# mcu-io.net
KiCad netlist of a schematic drawn in Altium Designer
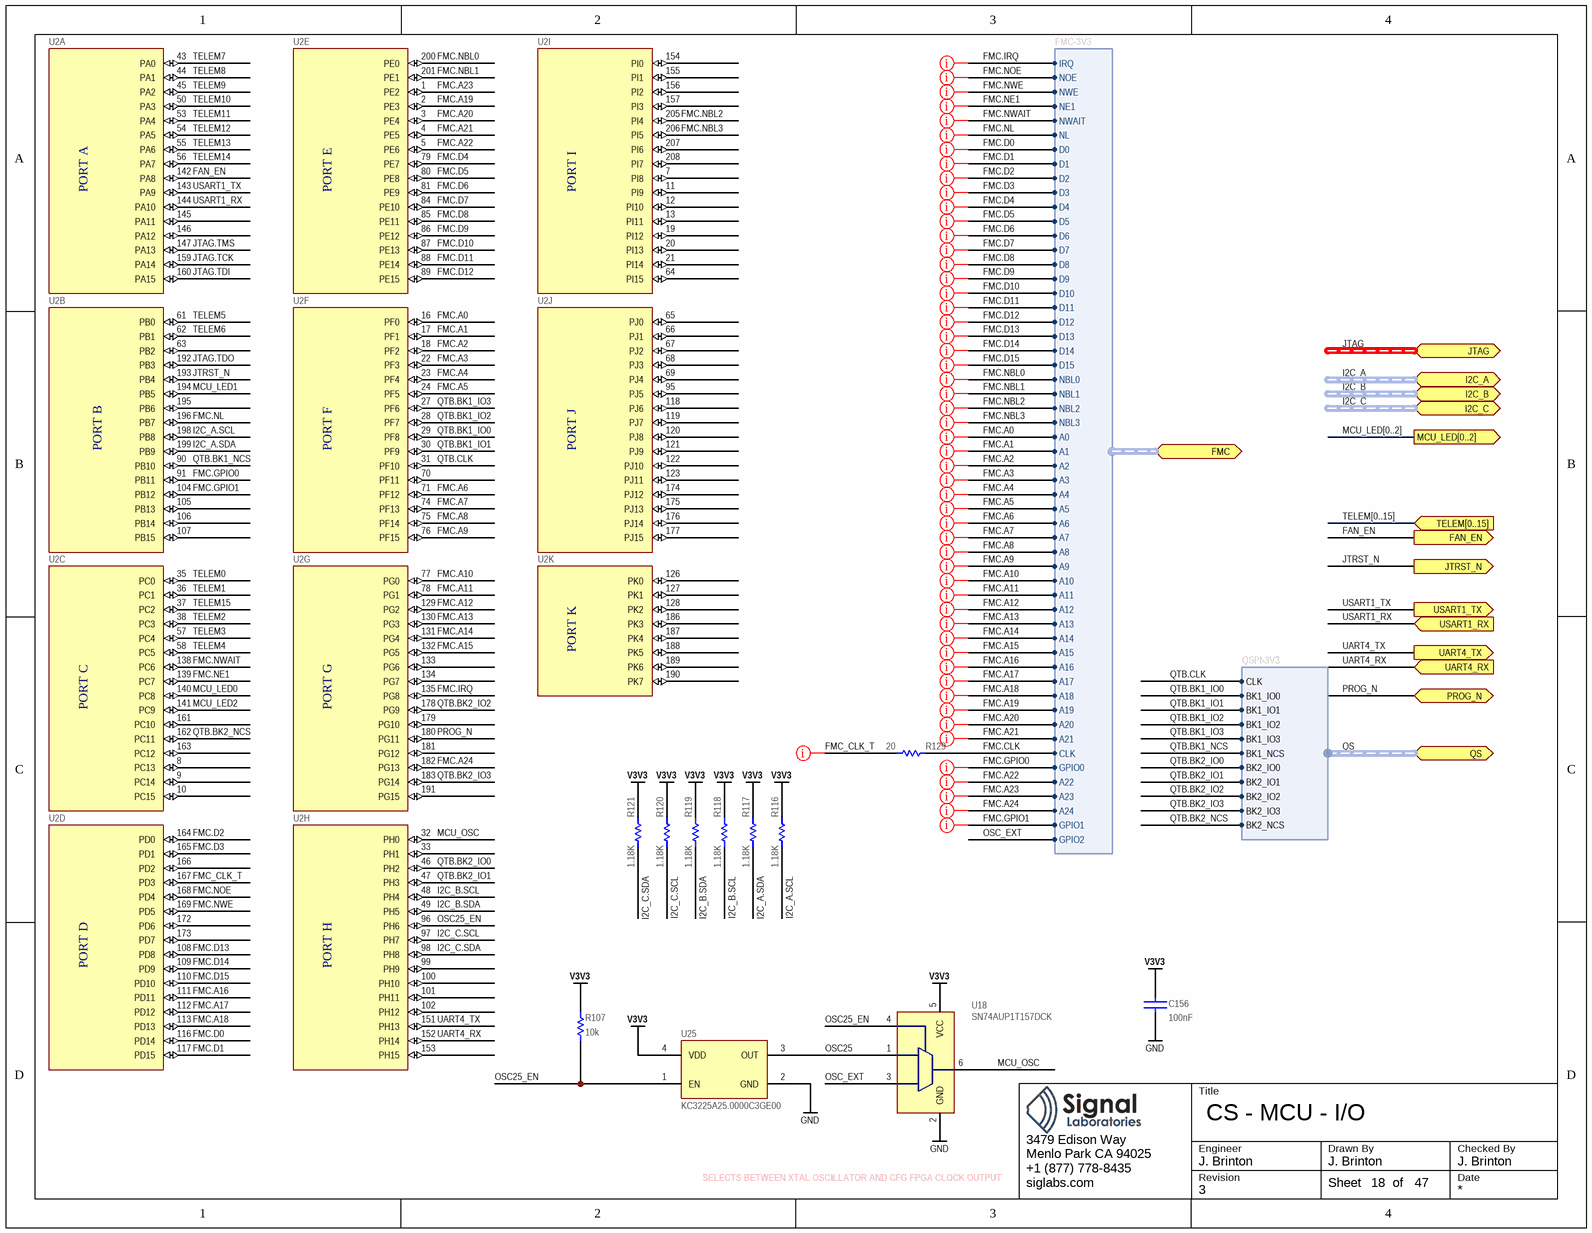
[diagram p0: mcu-io.SchDoc]

(export (version "E")
  (design (tool "Eeschema 10.0.6"))
  (components
    (comp (ref "C156")
      (value "100nF")
      (footprint "CAPC100X50X55L25N")
      (description "Ceramic Capacitor 100nF ±10% 50V X7R 0402")
      (fields (field (name "VOLTAGE") "50V") (field (name "MANUFACTURER") "Murata"))
      (libsource (lib "generic") (part "CAP"))
    )
    (comp (ref "R107")
      (value "10k")
      (footprint "RESC1005X40N")
      (description "Thick Film Resistor 10k ±1% 0.1W 50V 0402")
      (fields (field (name "MANUFACTURER") "Panasonic") (field (name "TOLERANCE") "±1%"))
      (libsource (lib "generic") (part "RES"))
    )
    (comp (ref "R116")
      (value "1.18K")
      (footprint "generic:RESC1005X40N")
      (description "Thick Film Resistor 1.18k ±1% 0402")
      (fields (field (name "MANUFACTURER") "Yageo") (field (name "TOLERANCE") "±1%"))
      (libsource (lib "Graviton") (part "RES 0402"))
    )
    (comp (ref "R117")
      (value "1.18K")
      (footprint "generic:RESC1005X40N")
      (description "Thick Film Resistor 1.18k ±1% 0402")
      (fields (field (name "MANUFACTURER") "Yageo") (field (name "TOLERANCE") "±1%"))
      (libsource (lib "Graviton") (part "RES 0402"))
    )
    (comp (ref "R118")
      (value "1.18K")
      (footprint "generic:RESC1005X40N")
      (description "Thick Film Resistor 1.18k ±1% 0402")
      (fields (field (name "MANUFACTURER") "Yageo") (field (name "TOLERANCE") "±1%"))
      (libsource (lib "Graviton") (part "RES 0402"))
    )
    (comp (ref "R119")
      (value "1.18K")
      (footprint "generic:RESC1005X40N")
      (description "Thick Film Resistor 1.18k ±1% 0402")
      (fields (field (name "MANUFACTURER") "Yageo") (field (name "TOLERANCE") "±1%"))
      (libsource (lib "Graviton") (part "RES 0402"))
    )
    (comp (ref "R120")
      (value "1.18K")
      (footprint "generic:RESC1005X40N")
      (description "Thick Film Resistor 1.18k ±1% 0402")
      (fields (field (name "MANUFACTURER") "Yageo") (field (name "TOLERANCE") "±1%"))
      (libsource (lib "Graviton") (part "RES 0402"))
    )
    (comp (ref "R121")
      (value "1.18K")
      (footprint "generic:RESC1005X40N")
      (description "Thick Film Resistor 1.18k ±1% 0402")
      (fields (field (name "MANUFACTURER") "Yageo") (field (name "TOLERANCE") "±1%"))
      (libsource (lib "Graviton") (part "RES 0402"))
    )
    (comp (ref "R129")
      (value "20")
      (footprint "RESC1005X40N")
      (description "Thick Film Resistor 20 ±1% 0.1W 75V 0402")
      (fields (field (name "TOLERANCE") "±1%") (field (name "MANUFACTURER") "Panasonic"))
      (libsource (lib "generic") (part "RES"))
    )
    (comp (ref "U2")
      (value "STM32F779BI")
      (footprint "LQFP208")
      (description "STM32 Microcontroller")
      (fields (field (name "MANUFACTURER") "ST Microelectronics"))
      (libsource (lib "hadley") (part "STM32F746BGT6"))
    )
    (comp (ref "U18")
      (value "SN74AUP1T157DCK")
      (footprint "generic:SOT363")
      (description "Buffer Multiplexer")
      (fields (field (name "MANUFACTURER") "Texas Instruments"))
      (libsource (lib "ti") (part "SN74AUP1T157DCK"))
    )
    (comp (ref "U25")
      (value "KC3225A25.0000C3GE00")
      (footprint "OSCCC320X250X80L75X100N")
      (description "Oscillator 25.00Mhz, -+50PPM, 3.3V")
      (fields (field (name "MANUFACTURER") "Kyocera"))
      (libsource (lib "MCD_TOOLS") (part "OSC_25M_NZ2520SB"))
    )
  )
  (nets
    (net (code "7") (name "/FAN_EN") (class "Default")
      (node (ref "U2") (pin "142") (pinfunction "PA8_142") (pintype "bidirectional"))
    )
    (net (code "8") (name "/FMC.A0") (class "Default")
      (node (ref "U2") (pin "16") (pinfunction "PF0_16") (pintype "bidirectional"))
    )
    (net (code "9") (name "/FMC.A1") (class "Default")
      (node (ref "U2") (pin "17") (pinfunction "PF1_17") (pintype "bidirectional"))
    )
    (net (code "10") (name "/FMC.A2") (class "Default")
      (node (ref "U2") (pin "18") (pinfunction "PF2_18") (pintype "bidirectional"))
    )
    (net (code "11") (name "/FMC.A3") (class "Default")
      (node (ref "U2") (pin "22") (pinfunction "PF3_22") (pintype "bidirectional"))
    )
    (net (code "12") (name "/FMC.A4") (class "Default")
      (node (ref "U2") (pin "23") (pinfunction "PF4_23") (pintype "bidirectional"))
    )
    (net (code "13") (name "/FMC.A5") (class "Default")
      (node (ref "U2") (pin "24") (pinfunction "PF5_24") (pintype "bidirectional"))
    )
    (net (code "14") (name "/FMC.A6") (class "Default")
      (node (ref "U2") (pin "71") (pinfunction "PF12_71") (pintype "bidirectional"))
    )
    (net (code "15") (name "/FMC.A7") (class "Default")
      (node (ref "U2") (pin "74") (pinfunction "PF13_74") (pintype "bidirectional"))
    )
    (net (code "16") (name "/FMC.A8") (class "Default")
      (node (ref "U2") (pin "75") (pinfunction "PF14_75") (pintype "bidirectional"))
    )
    (net (code "17") (name "/FMC.A9") (class "Default")
      (node (ref "U2") (pin "76") (pinfunction "PF15_76") (pintype "bidirectional"))
    )
    (net (code "18") (name "/FMC.A10") (class "Default")
      (node (ref "U2") (pin "77") (pinfunction "PG0_77") (pintype "bidirectional"))
    )
    (net (code "19") (name "/FMC.A11") (class "Default")
      (node (ref "U2") (pin "78") (pinfunction "PG1_78") (pintype "bidirectional"))
    )
    (net (code "20") (name "/FMC.A12") (class "Default")
      (node (ref "U2") (pin "129") (pinfunction "PG2_129") (pintype "bidirectional"))
    )
    (net (code "21") (name "/FMC.A13") (class "Default")
      (node (ref "U2") (pin "130") (pinfunction "PG3_130") (pintype "bidirectional"))
    )
    (net (code "22") (name "/FMC.A14") (class "Default")
      (node (ref "U2") (pin "131") (pinfunction "PG4_131") (pintype "bidirectional"))
    )
    (net (code "23") (name "/FMC.A15") (class "Default")
      (node (ref "U2") (pin "132") (pinfunction "PG5_132") (pintype "bidirectional"))
    )
    (net (code "24") (name "/FMC.A16") (class "Default")
      (node (ref "U2") (pin "111") (pinfunction "PD11_111") (pintype "bidirectional"))
    )
    (net (code "25") (name "/FMC.A17") (class "Default")
      (node (ref "U2") (pin "112") (pinfunction "PD12_112") (pintype "bidirectional"))
    )
    (net (code "26") (name "/FMC.A18") (class "Default")
      (node (ref "U2") (pin "113") (pinfunction "PD13_113") (pintype "bidirectional"))
    )
    (net (code "27") (name "/FMC.A19") (class "Default")
      (node (ref "U2") (pin "2") (pinfunction "PE3_2") (pintype "bidirectional"))
    )
    (net (code "28") (name "/FMC.A20") (class "Default")
      (node (ref "U2") (pin "3") (pinfunction "PE4_3") (pintype "bidirectional"))
    )
    (net (code "29") (name "/FMC.A21") (class "Default")
      (node (ref "U2") (pin "4") (pinfunction "PE5_4") (pintype "bidirectional"))
    )
    (net (code "30") (name "/FMC.A22") (class "Default")
      (node (ref "U2") (pin "5") (pinfunction "PE6_5") (pintype "bidirectional"))
    )
    (net (code "31") (name "/FMC.A23") (class "Default")
      (node (ref "U2") (pin "1") (pinfunction "PE2_1") (pintype "bidirectional"))
    )
    (net (code "32") (name "/FMC.A24") (class "Default")
      (node (ref "U2") (pin "182") (pinfunction "PG13_182") (pintype "bidirectional"))
    )
    (net (code "33") (name "/FMC.CLK") (class "Default")
      (node (ref "R129") (pin "2") (pinfunction "2_2") (pintype "passive"))
    )
    (net (code "34") (name "/FMC.D0") (class "Default")
      (node (ref "U2") (pin "116") (pinfunction "PD14_116") (pintype "bidirectional"))
    )
    (net (code "35") (name "/FMC.D1") (class "Default")
      (node (ref "U2") (pin "117") (pinfunction "PD15_117") (pintype "bidirectional"))
    )
    (net (code "36") (name "/FMC.D2") (class "Default")
      (node (ref "U2") (pin "164") (pinfunction "PD0_164") (pintype "bidirectional"))
    )
    (net (code "37") (name "/FMC.D3") (class "Default")
      (node (ref "U2") (pin "165") (pinfunction "PD1_165") (pintype "bidirectional"))
    )
    (net (code "38") (name "/FMC.D4") (class "Default")
      (node (ref "U2") (pin "79") (pinfunction "PE7_79") (pintype "bidirectional"))
    )
    (net (code "39") (name "/FMC.D5") (class "Default")
      (node (ref "U2") (pin "80") (pinfunction "PE8_80") (pintype "bidirectional"))
    )
    (net (code "40") (name "/FMC.D6") (class "Default")
      (node (ref "U2") (pin "81") (pinfunction "PE9_81") (pintype "bidirectional"))
    )
    (net (code "41") (name "/FMC.D7") (class "Default")
      (node (ref "U2") (pin "84") (pinfunction "PE10_84") (pintype "bidirectional"))
    )
    (net (code "42") (name "/FMC.D8") (class "Default")
      (node (ref "U2") (pin "85") (pinfunction "PE11_85") (pintype "bidirectional"))
    )
    (net (code "43") (name "/FMC.D9") (class "Default")
      (node (ref "U2") (pin "86") (pinfunction "PE12_86") (pintype "bidirectional"))
    )
    (net (code "44") (name "/FMC.D10") (class "Default")
      (node (ref "U2") (pin "87") (pinfunction "PE13_87") (pintype "bidirectional"))
    )
    (net (code "45") (name "/FMC.D11") (class "Default")
      (node (ref "U2") (pin "88") (pinfunction "PE14_88") (pintype "bidirectional"))
    )
    (net (code "46") (name "/FMC.D12") (class "Default")
      (node (ref "U2") (pin "89") (pinfunction "PE15_89") (pintype "bidirectional"))
    )
    (net (code "47") (name "/FMC.D13") (class "Default")
      (node (ref "U2") (pin "108") (pinfunction "PD8_108") (pintype "bidirectional"))
    )
    (net (code "48") (name "/FMC.D14") (class "Default")
      (node (ref "U2") (pin "109") (pinfunction "PD9_109") (pintype "bidirectional"))
    )
    (net (code "49") (name "/FMC.D15") (class "Default")
      (node (ref "U2") (pin "110") (pinfunction "PD10_110") (pintype "bidirectional"))
    )
    (net (code "50") (name "/FMC.GPIO0") (class "Default")
      (node (ref "U2") (pin "91") (pinfunction "PB11_91") (pintype "bidirectional"))
    )
    (net (code "51") (name "/FMC.GPIO1") (class "Default")
      (node (ref "U2") (pin "104") (pinfunction "PB12_104") (pintype "bidirectional"))
    )
    (net (code "52") (name "/FMC.IRQ") (class "Default")
      (node (ref "U2") (pin "135") (pinfunction "PG8_135") (pintype "bidirectional"))
    )
    (net (code "53") (name "/FMC.NBL0") (class "Default")
      (node (ref "U2") (pin "200") (pinfunction "PE0_200") (pintype "bidirectional"))
    )
    (net (code "54") (name "/FMC.NBL1") (class "Default")
      (node (ref "U2") (pin "201") (pinfunction "PE1_201") (pintype "bidirectional"))
    )
    (net (code "55") (name "/FMC.NBL2") (class "Default")
      (node (ref "U2") (pin "205") (pinfunction "PI4_205") (pintype "bidirectional"))
    )
    (net (code "56") (name "/FMC.NBL3") (class "Default")
      (node (ref "U2") (pin "206") (pinfunction "PI5_206") (pintype "bidirectional"))
    )
    (net (code "57") (name "/FMC.NE1") (class "Default")
      (node (ref "U2") (pin "139") (pinfunction "PC7_139") (pintype "bidirectional"))
    )
    (net (code "58") (name "/FMC.NL") (class "Default")
      (node (ref "U2") (pin "196") (pinfunction "PB7_196") (pintype "bidirectional"))
    )
    (net (code "59") (name "/FMC.NOE") (class "Default")
      (node (ref "U2") (pin "168") (pinfunction "PD4_168") (pintype "bidirectional"))
    )
    (net (code "60") (name "/FMC.NWAIT") (class "Default")
      (node (ref "U2") (pin "138") (pinfunction "PC6_138") (pintype "bidirectional"))
    )
    (net (code "61") (name "/FMC.NWE") (class "Default")
      (node (ref "U2") (pin "169") (pinfunction "PD5_169") (pintype "bidirectional"))
    )
    (net (code "62") (name "/FMC_CLK_T") (class "Default")
      (node (ref "R129") (pin "1") (pinfunction "1_1") (pintype "passive"))
      (node (ref "U2") (pin "167") (pinfunction "PD3_167") (pintype "bidirectional"))
    )
    (net (code "63") (name "/I2C_A.SCL") (class "Default")
      (node (ref "R116") (pin "1") (pinfunction "1_1") (pintype "passive"))
      (node (ref "U2") (pin "198") (pinfunction "PB8_198") (pintype "bidirectional"))
    )
    (net (code "64") (name "/I2C_A.SDA") (class "Default")
      (node (ref "R117") (pin "1") (pinfunction "1_1") (pintype "passive"))
      (node (ref "U2") (pin "199") (pinfunction "PB9_199") (pintype "bidirectional"))
    )
    (net (code "65") (name "/I2C_B.SCL") (class "Default")
      (node (ref "R118") (pin "1") (pinfunction "1_1") (pintype "passive"))
      (node (ref "U2") (pin "48") (pinfunction "PH4_48") (pintype "bidirectional"))
    )
    (net (code "66") (name "/I2C_B.SDA") (class "Default")
      (node (ref "R119") (pin "1") (pinfunction "1_1") (pintype "passive"))
      (node (ref "U2") (pin "49") (pinfunction "PH5_49") (pintype "bidirectional"))
    )
    (net (code "67") (name "/I2C_C.SCL") (class "Default")
      (node (ref "R120") (pin "1") (pinfunction "1_1") (pintype "passive"))
      (node (ref "U2") (pin "97") (pinfunction "PH7_97") (pintype "bidirectional"))
    )
    (net (code "68") (name "/I2C_C.SDA") (class "Default")
      (node (ref "R121") (pin "1") (pinfunction "1_1") (pintype "passive"))
      (node (ref "U2") (pin "98") (pinfunction "PH8_98") (pintype "bidirectional"))
    )
    (net (code "69") (name "/JTAG.TCK") (class "Default")
      (node (ref "U2") (pin "159") (pinfunction "PA14_159") (pintype "bidirectional"))
    )
    (net (code "70") (name "/JTAG.TDI") (class "Default")
      (node (ref "U2") (pin "160") (pinfunction "PA15_160") (pintype "bidirectional"))
    )
    (net (code "71") (name "/JTAG.TDO") (class "Default")
      (node (ref "U2") (pin "192") (pinfunction "PB3_192") (pintype "bidirectional"))
    )
    (net (code "72") (name "/JTAG.TMS") (class "Default")
      (node (ref "U2") (pin "147") (pinfunction "PA13_147") (pintype "bidirectional"))
    )
    (net (code "73") (name "/JTRST_N") (class "Default")
      (node (ref "U2") (pin "193") (pinfunction "PB4_193") (pintype "bidirectional"))
    )
    (net (code "74") (name "/MCU_LED0") (class "Default")
      (node (ref "U2") (pin "140") (pinfunction "PC8_140") (pintype "bidirectional"))
    )
    (net (code "75") (name "/MCU_LED1") (class "Default")
      (node (ref "U2") (pin "194") (pinfunction "PB5_194") (pintype "bidirectional"))
    )
    (net (code "76") (name "/MCU_LED2") (class "Default")
      (node (ref "U2") (pin "141") (pinfunction "PC9_141") (pintype "bidirectional"))
    )
    (net (code "78") (name "/MCU_OSC") (class "Default")
      (node (ref "U18") (pin "6") (pinfunction "Y_6") (pintype "passive"))
      (node (ref "U2") (pin "32") (pinfunction "PH0_32") (pintype "bidirectional"))
    )
    (net (code "79") (name "/OSC25") (class "Default")
      (node (ref "U18") (pin "1") (pinfunction "A_1") (pintype "passive"))
      (node (ref "U25") (pin "3") (pinfunction "OUT_3") (pintype "passive"))
    )
    (net (code "80") (name "/OSC25_EN") (class "Default")
      (node (ref "R107") (pin "1") (pinfunction "1_1") (pintype "passive"))
      (node (ref "U18") (pin "4") (pinfunction "C_4") (pintype "passive"))
      (node (ref "U2") (pin "96") (pinfunction "PH6_96") (pintype "bidirectional"))
      (node (ref "U25") (pin "1") (pinfunction "EN_1") (pintype "passive"))
    )
    (net (code "81") (name "/OSC_EXT") (class "Default")
      (node (ref "U18") (pin "3") (pinfunction "B_3") (pintype "passive"))
    )
    (net (code "82") (name "/PROG_N") (class "Default")
      (node (ref "U2") (pin "180") (pinfunction "PG11_180") (pintype "bidirectional"))
    )
    (net (code "84") (name "/QTB.BK1_IO0") (class "Default")
      (node (ref "U2") (pin "29") (pinfunction "PF8_29") (pintype "bidirectional"))
    )
    (net (code "85") (name "/QTB.BK1_IO1") (class "Default")
      (node (ref "U2") (pin "30") (pinfunction "PF9_30") (pintype "bidirectional"))
    )
    (net (code "86") (name "/QTB.BK1_IO2") (class "Default")
      (node (ref "U2") (pin "28") (pinfunction "PF7_28") (pintype "bidirectional"))
    )
    (net (code "87") (name "/QTB.BK1_IO3") (class "Default")
      (node (ref "U2") (pin "27") (pinfunction "PF6_27") (pintype "bidirectional"))
    )
    (net (code "88") (name "/QTB.BK1_NCS") (class "Default")
      (node (ref "U2") (pin "90") (pinfunction "PB10_90") (pintype "bidirectional"))
    )
    (net (code "89") (name "/QTB.BK2_IO0") (class "Default")
      (node (ref "U2") (pin "46") (pinfunction "PH2_46") (pintype "bidirectional"))
    )
    (net (code "90") (name "/QTB.BK2_IO1") (class "Default")
      (node (ref "U2") (pin "47") (pinfunction "PH3_47") (pintype "bidirectional"))
    )
    (net (code "91") (name "/QTB.BK2_IO2") (class "Default")
      (node (ref "U2") (pin "178") (pinfunction "PG9_178") (pintype "bidirectional"))
    )
    (net (code "92") (name "/QTB.BK2_IO3") (class "Default")
      (node (ref "U2") (pin "183") (pinfunction "PG14_183") (pintype "bidirectional"))
    )
    (net (code "93") (name "/QTB.BK2_NCS") (class "Default")
      (node (ref "U2") (pin "162") (pinfunction "PC11_162") (pintype "bidirectional"))
    )
    (net (code "94") (name "/QTB.CLK") (class "Default")
      (node (ref "U2") (pin "31") (pinfunction "PF10_31") (pintype "bidirectional"))
    )
    (net (code "95") (name "/TELEM0") (class "Default")
      (node (ref "U2") (pin "35") (pinfunction "PC0_35") (pintype "bidirectional"))
    )
    (net (code "96") (name "/TELEM1") (class "Default")
      (node (ref "U2") (pin "36") (pinfunction "PC1_36") (pintype "bidirectional"))
    )
    (net (code "97") (name "/TELEM2") (class "Default")
      (node (ref "U2") (pin "38") (pinfunction "PC3_38") (pintype "bidirectional"))
    )
    (net (code "98") (name "/TELEM3") (class "Default")
      (node (ref "U2") (pin "57") (pinfunction "PC4_57") (pintype "bidirectional"))
    )
    (net (code "99") (name "/TELEM4") (class "Default")
      (node (ref "U2") (pin "58") (pinfunction "PC5_58") (pintype "bidirectional"))
    )
    (net (code "100") (name "/TELEM5") (class "Default")
      (node (ref "U2") (pin "61") (pinfunction "PB0_61") (pintype "bidirectional"))
    )
    (net (code "101") (name "/TELEM6") (class "Default")
      (node (ref "U2") (pin "62") (pinfunction "PB1_62") (pintype "bidirectional"))
    )
    (net (code "102") (name "/TELEM7") (class "Default")
      (node (ref "U2") (pin "43") (pinfunction "PA0_43") (pintype "bidirectional"))
    )
    (net (code "103") (name "/TELEM8") (class "Default")
      (node (ref "U2") (pin "44") (pinfunction "PA1_44") (pintype "bidirectional"))
    )
    (net (code "104") (name "/TELEM9") (class "Default")
      (node (ref "U2") (pin "45") (pinfunction "PA2_45") (pintype "bidirectional"))
    )
    (net (code "105") (name "/TELEM10") (class "Default")
      (node (ref "U2") (pin "50") (pinfunction "PA3_50") (pintype "bidirectional"))
    )
    (net (code "106") (name "/TELEM11") (class "Default")
      (node (ref "U2") (pin "53") (pinfunction "PA4_53") (pintype "bidirectional"))
    )
    (net (code "107") (name "/TELEM12") (class "Default")
      (node (ref "U2") (pin "54") (pinfunction "PA5_54") (pintype "bidirectional"))
    )
    (net (code "108") (name "/TELEM13") (class "Default")
      (node (ref "U2") (pin "55") (pinfunction "PA6_55") (pintype "bidirectional"))
    )
    (net (code "109") (name "/TELEM14") (class "Default")
      (node (ref "U2") (pin "56") (pinfunction "PA7_56") (pintype "bidirectional"))
    )
    (net (code "110") (name "/TELEM15") (class "Default")
      (node (ref "U2") (pin "37") (pinfunction "PC2_37") (pintype "bidirectional"))
    )
    (net (code "112") (name "/UART4_RX") (class "Default")
      (node (ref "U2") (pin "152") (pinfunction "PH14_152") (pintype "bidirectional"))
    )
    (net (code "113") (name "/UART4_TX") (class "Default")
      (node (ref "U2") (pin "151") (pinfunction "PH13_151") (pintype "bidirectional"))
    )
    (net (code "114") (name "/USART1_RX") (class "Default")
      (node (ref "U2") (pin "144") (pinfunction "PA10_144") (pintype "bidirectional"))
    )
    (net (code "115") (name "/USART1_TX") (class "Default")
      (node (ref "U2") (pin "143") (pinfunction "PA9_143") (pintype "bidirectional"))
    )
    (net (code "121") (name "GND") (class "Default")
      (node (ref "C156") (pin "1") (pinfunction "1_1") (pintype "passive"))
      (node (ref "U18") (pin "2") (pinfunction "GND_2") (pintype "passive"))
      (node (ref "U25") (pin "2") (pinfunction "GND_2") (pintype "passive"))
    )
    (net (code "122") (name "V3V3") (class "Default")
      (node (ref "C156") (pin "2") (pinfunction "2_2") (pintype "passive"))
      (node (ref "R107") (pin "2") (pinfunction "2_2") (pintype "passive"))
      (node (ref "R116") (pin "2") (pinfunction "2_2") (pintype "passive"))
      (node (ref "R117") (pin "2") (pinfunction "2_2") (pintype "passive"))
      (node (ref "R118") (pin "2") (pinfunction "2_2") (pintype "passive"))
      (node (ref "R119") (pin "2") (pinfunction "2_2") (pintype "passive"))
      (node (ref "R120") (pin "2") (pinfunction "2_2") (pintype "passive"))
      (node (ref "R121") (pin "2") (pinfunction "2_2") (pintype "passive"))
      (node (ref "U18") (pin "5") (pinfunction "VCC_5") (pintype "passive"))
      (node (ref "U25") (pin "4") (pinfunction "VDD_4") (pintype "passive"))
    )
    (net (code "123") (name "unconnected-(U2A-PA11-Pad145)") (class "Default")
      (node (ref "U2") (pin "145") (pinfunction "PA11_145") (pintype "bidirectional"))
    )
    (net (code "124") (name "unconnected-(U2A-PA12-Pad146)") (class "Default")
      (node (ref "U2") (pin "146") (pinfunction "PA12_146") (pintype "bidirectional"))
    )
    (net (code "125") (name "unconnected-(U2B-PB2-Pad63)") (class "Default")
      (node (ref "U2") (pin "63") (pinfunction "PB2_63") (pintype "bidirectional"))
    )
    (net (code "126") (name "unconnected-(U2B-PB6-Pad195)") (class "Default")
      (node (ref "U2") (pin "195") (pinfunction "PB6_195") (pintype "bidirectional"))
    )
    (net (code "127") (name "unconnected-(U2B-PB13-Pad105)") (class "Default")
      (node (ref "U2") (pin "105") (pinfunction "PB13_105") (pintype "bidirectional"))
    )
    (net (code "128") (name "unconnected-(U2B-PB14-Pad106)") (class "Default")
      (node (ref "U2") (pin "106") (pinfunction "PB14_106") (pintype "bidirectional"))
    )
    (net (code "129") (name "unconnected-(U2B-PB15-Pad107)") (class "Default")
      (node (ref "U2") (pin "107") (pinfunction "PB15_107") (pintype "bidirectional"))
    )
    (net (code "130") (name "unconnected-(U2C-PC10-Pad161)") (class "Default")
      (node (ref "U2") (pin "161") (pinfunction "PC10_161") (pintype "bidirectional"))
    )
    (net (code "131") (name "unconnected-(U2C-PC12-Pad163)") (class "Default")
      (node (ref "U2") (pin "163") (pinfunction "PC12_163") (pintype "bidirectional"))
    )
    (net (code "132") (name "unconnected-(U2C-PC13-Pad8)") (class "Default")
      (node (ref "U2") (pin "8") (pinfunction "PC13_8") (pintype "bidirectional"))
    )
    (net (code "133") (name "unconnected-(U2C-PC14-Pad9)") (class "Default")
      (node (ref "U2") (pin "9") (pinfunction "PC14_9") (pintype "bidirectional"))
    )
    (net (code "134") (name "unconnected-(U2C-PC15-Pad10)") (class "Default")
      (node (ref "U2") (pin "10") (pinfunction "PC15_10") (pintype "bidirectional"))
    )
    (net (code "135") (name "unconnected-(U2D-PD2-Pad166)") (class "Default")
      (node (ref "U2") (pin "166") (pinfunction "PD2_166") (pintype "bidirectional"))
    )
    (net (code "136") (name "unconnected-(U2D-PD6-Pad172)") (class "Default")
      (node (ref "U2") (pin "172") (pinfunction "PD6_172") (pintype "bidirectional"))
    )
    (net (code "137") (name "unconnected-(U2D-PD7-Pad173)") (class "Default")
      (node (ref "U2") (pin "173") (pinfunction "PD7_173") (pintype "bidirectional"))
    )
    (net (code "138") (name "unconnected-(U2F-PF11-Pad70)") (class "Default")
      (node (ref "U2") (pin "70") (pinfunction "PF11_70") (pintype "bidirectional"))
    )
    (net (code "139") (name "unconnected-(U2G-PG6-Pad133)") (class "Default")
      (node (ref "U2") (pin "133") (pinfunction "PG6_133") (pintype "bidirectional"))
    )
    (net (code "140") (name "unconnected-(U2G-PG7-Pad134)") (class "Default")
      (node (ref "U2") (pin "134") (pinfunction "PG7_134") (pintype "bidirectional"))
    )
    (net (code "141") (name "unconnected-(U2G-PG10-Pad179)") (class "Default")
      (node (ref "U2") (pin "179") (pinfunction "PG10_179") (pintype "bidirectional"))
    )
    (net (code "142") (name "unconnected-(U2G-PG12-Pad181)") (class "Default")
      (node (ref "U2") (pin "181") (pinfunction "PG12_181") (pintype "bidirectional"))
    )
    (net (code "143") (name "unconnected-(U2G-PG15-Pad191)") (class "Default")
      (node (ref "U2") (pin "191") (pinfunction "PG15_191") (pintype "bidirectional"))
    )
    (net (code "144") (name "unconnected-(U2H-PH1-Pad33)") (class "Default")
      (node (ref "U2") (pin "33") (pinfunction "PH1_33") (pintype "bidirectional"))
    )
    (net (code "145") (name "unconnected-(U2H-PH9-Pad99)") (class "Default")
      (node (ref "U2") (pin "99") (pinfunction "PH9_99") (pintype "bidirectional"))
    )
    (net (code "146") (name "unconnected-(U2H-PH10-Pad100)") (class "Default")
      (node (ref "U2") (pin "100") (pinfunction "PH10_100") (pintype "bidirectional"))
    )
    (net (code "147") (name "unconnected-(U2H-PH11-Pad101)") (class "Default")
      (node (ref "U2") (pin "101") (pinfunction "PH11_101") (pintype "bidirectional"))
    )
    (net (code "148") (name "unconnected-(U2H-PH12-Pad102)") (class "Default")
      (node (ref "U2") (pin "102") (pinfunction "PH12_102") (pintype "bidirectional"))
    )
    (net (code "149") (name "unconnected-(U2H-PH15-Pad153)") (class "Default")
      (node (ref "U2") (pin "153") (pinfunction "PH15_153") (pintype "bidirectional"))
    )
    (net (code "150") (name "unconnected-(U2I-PI0-Pad154)") (class "Default")
      (node (ref "U2") (pin "154") (pinfunction "PI0_154") (pintype "bidirectional"))
    )
    (net (code "151") (name "unconnected-(U2I-PI1-Pad155)") (class "Default")
      (node (ref "U2") (pin "155") (pinfunction "PI1_155") (pintype "bidirectional"))
    )
    (net (code "152") (name "unconnected-(U2I-PI2-Pad156)") (class "Default")
      (node (ref "U2") (pin "156") (pinfunction "PI2_156") (pintype "bidirectional"))
    )
    (net (code "153") (name "unconnected-(U2I-PI3-Pad157)") (class "Default")
      (node (ref "U2") (pin "157") (pinfunction "PI3_157") (pintype "bidirectional"))
    )
    (net (code "154") (name "unconnected-(U2I-PI6-Pad207)") (class "Default")
      (node (ref "U2") (pin "207") (pinfunction "PI6_207") (pintype "bidirectional"))
    )
    (net (code "155") (name "unconnected-(U2I-PI7-Pad208)") (class "Default")
      (node (ref "U2") (pin "208") (pinfunction "PI7_208") (pintype "bidirectional"))
    )
    (net (code "156") (name "unconnected-(U2I-PI8-Pad7)") (class "Default")
      (node (ref "U2") (pin "7") (pinfunction "PI8_7") (pintype "bidirectional"))
    )
    (net (code "157") (name "unconnected-(U2I-PI9-Pad11)") (class "Default")
      (node (ref "U2") (pin "11") (pinfunction "PI9_11") (pintype "bidirectional"))
    )
    (net (code "158") (name "unconnected-(U2I-PI10-Pad12)") (class "Default")
      (node (ref "U2") (pin "12") (pinfunction "PI10_12") (pintype "bidirectional"))
    )
    (net (code "159") (name "unconnected-(U2I-PI11-Pad13)") (class "Default")
      (node (ref "U2") (pin "13") (pinfunction "PI11_13") (pintype "bidirectional"))
    )
    (net (code "160") (name "unconnected-(U2I-PI12-Pad19)") (class "Default")
      (node (ref "U2") (pin "19") (pinfunction "PI12_19") (pintype "bidirectional"))
    )
    (net (code "161") (name "unconnected-(U2I-PI13-Pad20)") (class "Default")
      (node (ref "U2") (pin "20") (pinfunction "PI13_20") (pintype "bidirectional"))
    )
    (net (code "162") (name "unconnected-(U2I-PI14-Pad21)") (class "Default")
      (node (ref "U2") (pin "21") (pinfunction "PI14_21") (pintype "bidirectional"))
    )
    (net (code "163") (name "unconnected-(U2I-PI15-Pad64)") (class "Default")
      (node (ref "U2") (pin "64") (pinfunction "PI15_64") (pintype "bidirectional"))
    )
    (net (code "164") (name "unconnected-(U2J-PJ0-Pad65)") (class "Default")
      (node (ref "U2") (pin "65") (pinfunction "PJ0_65") (pintype "bidirectional"))
    )
    (net (code "165") (name "unconnected-(U2J-PJ1-Pad66)") (class "Default")
      (node (ref "U2") (pin "66") (pinfunction "PJ1_66") (pintype "bidirectional"))
    )
    (net (code "166") (name "unconnected-(U2J-PJ2-Pad67)") (class "Default")
      (node (ref "U2") (pin "67") (pinfunction "PJ2_67") (pintype "bidirectional"))
    )
    (net (code "167") (name "unconnected-(U2J-PJ3-Pad68)") (class "Default")
      (node (ref "U2") (pin "68") (pinfunction "PJ3_68") (pintype "bidirectional"))
    )
    (net (code "168") (name "unconnected-(U2J-PJ4-Pad69)") (class "Default")
      (node (ref "U2") (pin "69") (pinfunction "PJ4_69") (pintype "bidirectional"))
    )
    (net (code "169") (name "unconnected-(U2J-PJ5-Pad95)") (class "Default")
      (node (ref "U2") (pin "95") (pinfunction "PJ5_95") (pintype "bidirectional"))
    )
    (net (code "170") (name "unconnected-(U2J-PJ6-Pad118)") (class "Default")
      (node (ref "U2") (pin "118") (pinfunction "PJ6_118") (pintype "bidirectional"))
    )
    (net (code "171") (name "unconnected-(U2J-PJ7-Pad119)") (class "Default")
      (node (ref "U2") (pin "119") (pinfunction "PJ7_119") (pintype "bidirectional"))
    )
    (net (code "172") (name "unconnected-(U2J-PJ8-Pad120)") (class "Default")
      (node (ref "U2") (pin "120") (pinfunction "PJ8_120") (pintype "bidirectional"))
    )
    (net (code "173") (name "unconnected-(U2J-PJ9-Pad121)") (class "Default")
      (node (ref "U2") (pin "121") (pinfunction "PJ9_121") (pintype "bidirectional"))
    )
    (net (code "174") (name "unconnected-(U2J-PJ10-Pad122)") (class "Default")
      (node (ref "U2") (pin "122") (pinfunction "PJ10_122") (pintype "bidirectional"))
    )
    (net (code "175") (name "unconnected-(U2J-PJ11-Pad123)") (class "Default")
      (node (ref "U2") (pin "123") (pinfunction "PJ11_123") (pintype "bidirectional"))
    )
    (net (code "176") (name "unconnected-(U2J-PJ12-Pad174)") (class "Default")
      (node (ref "U2") (pin "174") (pinfunction "PJ12_174") (pintype "bidirectional"))
    )
    (net (code "177") (name "unconnected-(U2J-PJ13-Pad175)") (class "Default")
      (node (ref "U2") (pin "175") (pinfunction "PJ13_175") (pintype "bidirectional"))
    )
    (net (code "178") (name "unconnected-(U2J-PJ14-Pad176)") (class "Default")
      (node (ref "U2") (pin "176") (pinfunction "PJ14_176") (pintype "bidirectional"))
    )
    (net (code "179") (name "unconnected-(U2J-PJ15-Pad177)") (class "Default")
      (node (ref "U2") (pin "177") (pinfunction "PJ15_177") (pintype "bidirectional"))
    )
    (net (code "180") (name "unconnected-(U2K-PK0-Pad126)") (class "Default")
      (node (ref "U2") (pin "126") (pinfunction "PK0_126") (pintype "bidirectional"))
    )
    (net (code "181") (name "unconnected-(U2K-PK1-Pad127)") (class "Default")
      (node (ref "U2") (pin "127") (pinfunction "PK1_127") (pintype "bidirectional"))
    )
    (net (code "182") (name "unconnected-(U2K-PK2-Pad128)") (class "Default")
      (node (ref "U2") (pin "128") (pinfunction "PK2_128") (pintype "bidirectional"))
    )
    (net (code "183") (name "unconnected-(U2K-PK3-Pad186)") (class "Default")
      (node (ref "U2") (pin "186") (pinfunction "PK3_186") (pintype "bidirectional"))
    )
    (net (code "184") (name "unconnected-(U2K-PK4-Pad187)") (class "Default")
      (node (ref "U2") (pin "187") (pinfunction "PK4_187") (pintype "bidirectional"))
    )
    (net (code "185") (name "unconnected-(U2K-PK5-Pad188)") (class "Default")
      (node (ref "U2") (pin "188") (pinfunction "PK5_188") (pintype "bidirectional"))
    )
    (net (code "186") (name "unconnected-(U2K-PK6-Pad189)") (class "Default")
      (node (ref "U2") (pin "189") (pinfunction "PK6_189") (pintype "bidirectional"))
    )
    (net (code "187") (name "unconnected-(U2K-PK7-Pad190)") (class "Default")
      (node (ref "U2") (pin "190") (pinfunction "PK7_190") (pintype "bidirectional"))
    )
  )
)
